# tv_b_gone_extended_schematic.net
KiCad netlist of a schematic drawn in EAGLE
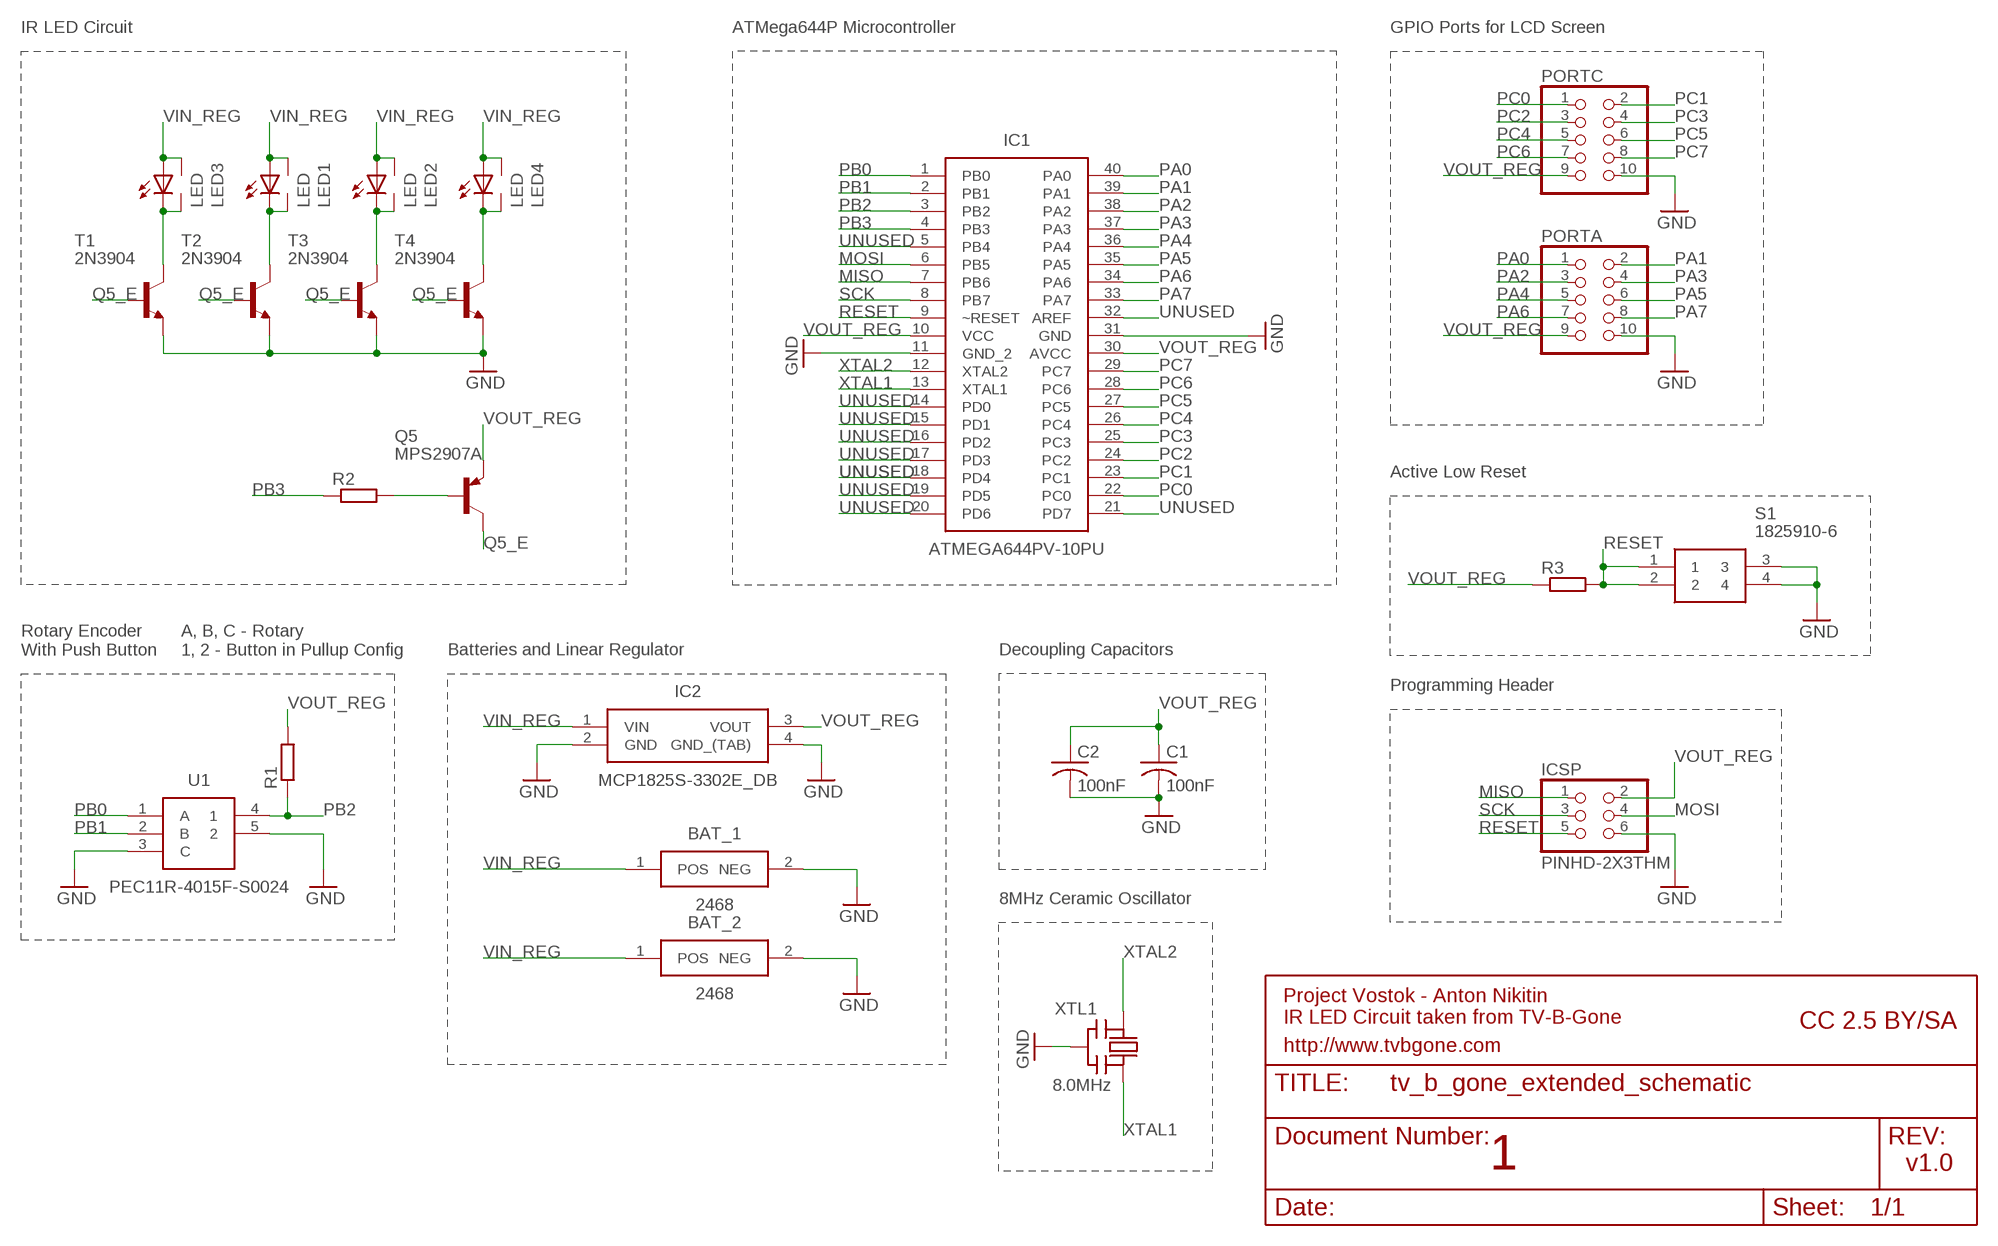
[diagram p0: schematic, sheet 1]

(export (version "E")
  (design (tool "Eeschema 10.0.6"))
  (components
    (comp (ref "BAT_1")
      (value "2468")
      (footprint "eagle-import:2468")
      (fields (field (name "RS_PART_NUMBER") "2794965"))
      (libsource (lib "eagle-import") (part "2468"))
    )
    (comp (ref "BAT_2")
      (value "2468")
      (footprint "eagle-import:2468")
      (fields (field (name "RS_PART_NUMBER") "2794965"))
      (libsource (lib "eagle-import") (part "2468"))
    )
    (comp (ref "C1")
      (value "100nF")
      (footprint "eagle-import:C025-025X050")
      (libsource (lib "eagle-import") (part "C-US025-025X050"))
    )
    (comp (ref "C2")
      (value "100nF")
      (footprint "eagle-import:C025-025X050")
      (libsource (lib "eagle-import") (part "C-US025-025X050"))
    )
    (comp (ref "IC1")
      (value "ATMEGA644PV-10PU")
      (footprint "eagle-import:DIP254P1524X483-40")
      (fields (field (name "RS_PART_NUMBER") "7380491P"))
      (libsource (lib "eagle-import") (part "ATMEGA644PV-10PU"))
    )
    (comp (ref "IC2")
      (value "MCP1825S-3302E_DB")
      (footprint "eagle-import:SOT230P700X180-4N")
      (fields
        (field (name "MANUFACTURER_PART_NUMBER") "MCP1825S-3302E/DB")
        (field (name "RS_PART_NUMBER") "9115520")
      )
      (libsource (lib "eagle-import") (part "MCP1825S-3302E_DB"))
    )
    (comp (ref "ICSP")
      (value "PINHD-2X3THM")
      (footprint "eagle-import:ISP6")
      (libsource (lib "eagle-import") (part "PINHD-2X3THM"))
    )
    (comp (ref "LED1")
      (value "LED")
      (footprint "eagle-import:5MM-SIDE")
      (libsource (lib "eagle-import") (part "LED"))
    )
    (comp (ref "LED2")
      (value "LED")
      (footprint "eagle-import:5MM-SIDE")
      (libsource (lib "eagle-import") (part "LED"))
    )
    (comp (ref "LED3")
      (value "LED")
      (footprint "eagle-import:5MM-SIDE")
      (libsource (lib "eagle-import") (part "LED"))
    )
    (comp (ref "LED4")
      (value "LED")
      (footprint "eagle-import:5MM-SIDE")
      (libsource (lib "eagle-import") (part "LED"))
    )
    (comp (ref "PORTA")
      (value "PINHD-2X5")
      (footprint "eagle-import:2X05")
      (libsource (lib "eagle-import") (part "PINHD-2X5"))
    )
    (comp (ref "PORTC")
      (value "PINHD-2X5")
      (footprint "eagle-import:2X05")
      (libsource (lib "eagle-import") (part "PINHD-2X5"))
    )
    (comp (ref "Q5")
      (value "MPS2907A")
      (footprint "eagle-import:TO92-CBE")
      (libsource (lib "eagle-import") (part "MPS2907A"))
    )
    (comp (ref "R1")
      (value "R-EU_0204/5")
      (footprint "eagle-import:0204_5")
      (libsource (lib "eagle-import") (part "resistor_348_R-EU_0204/5"))
    )
    (comp (ref "R2")
      (value "R-EU_0204/5")
      (footprint "eagle-import:0204_5")
      (libsource (lib "eagle-import") (part "resistor_348_R-EU_0204/5"))
    )
    (comp (ref "R3")
      (value "R-EU_0204/7")
      (footprint "eagle-import:0204_7")
      (libsource (lib "eagle-import") (part "R-EU_0204/7"))
    )
    (comp (ref "S1")
      (value "1825910-6")
      (footprint "eagle-import:1825910-6")
      (fields (field (name "RS_PART_NUMBER") "1613779"))
      (libsource (lib "eagle-import") (part "1825910-6"))
    )
    (comp (ref "T1")
      (value "2N3904")
      (footprint "eagle-import:TO92")
      (libsource (lib "eagle-import") (part "2N3904"))
    )
    (comp (ref "T2")
      (value "2N3904")
      (footprint "eagle-import:TO92")
      (libsource (lib "eagle-import") (part "2N3904"))
    )
    (comp (ref "T3")
      (value "2N3904")
      (footprint "eagle-import:TO92")
      (libsource (lib "eagle-import") (part "2N3904"))
    )
    (comp (ref "T4")
      (value "2N3904")
      (footprint "eagle-import:TO92")
      (libsource (lib "eagle-import") (part "2N3904"))
    )
    (comp (ref "U1")
      (value "PEC11R-4015F-S0024")
      (footprint "eagle-import:PEC12R-4XXXF-SXXXX_1")
      (fields (field (name "RS_PART_NUMBER") "7377739P"))
      (libsource (lib "eagle-import") (part "PEC11R-4015F-S0024"))
    )
    (comp (ref "XTL1")
      (value "8.0MHz")
      (footprint "eagle-import:CERM_OSC")
      (libsource (lib "eagle-import") (part "CERMOSCILL"))
    )
  )
  (nets
    (net (code "1") (name "/MISO") (class "Default")
      (node (ref "IC1") (pin "7") (pinfunction "PB6_7") (pintype "passive"))
      (node (ref "ICSP") (pin "1") (pinfunction "1_1") (pintype "passive"))
    )
    (net (code "2") (name "/MOSI") (class "Default")
      (node (ref "IC1") (pin "6") (pinfunction "PB5_6") (pintype "passive"))
      (node (ref "ICSP") (pin "4") (pinfunction "4_4") (pintype "passive"))
    )
    (net (code "3") (name "/PA0") (class "Default")
      (node (ref "IC1") (pin "40") (pinfunction "PA0_40") (pintype "passive"))
      (node (ref "PORTA") (pin "1") (pinfunction "1_1") (pintype "passive"))
    )
    (net (code "4") (name "/PA1") (class "Default")
      (node (ref "IC1") (pin "39") (pinfunction "PA1_39") (pintype "passive"))
      (node (ref "PORTA") (pin "2") (pinfunction "2_2") (pintype "passive"))
    )
    (net (code "5") (name "/PA2") (class "Default")
      (node (ref "IC1") (pin "38") (pinfunction "PA2_38") (pintype "passive"))
      (node (ref "PORTA") (pin "3") (pinfunction "3_3") (pintype "passive"))
    )
    (net (code "6") (name "/PA3") (class "Default")
      (node (ref "IC1") (pin "37") (pinfunction "PA3_37") (pintype "passive"))
      (node (ref "PORTA") (pin "4") (pinfunction "4_4") (pintype "passive"))
    )
    (net (code "7") (name "/PA4") (class "Default")
      (node (ref "IC1") (pin "36") (pinfunction "PA4_36") (pintype "passive"))
      (node (ref "PORTA") (pin "5") (pinfunction "5_5") (pintype "passive"))
    )
    (net (code "8") (name "/PA5") (class "Default")
      (node (ref "IC1") (pin "35") (pinfunction "PA5_35") (pintype "passive"))
      (node (ref "PORTA") (pin "6") (pinfunction "6_6") (pintype "passive"))
    )
    (net (code "9") (name "/PA6") (class "Default")
      (node (ref "IC1") (pin "34") (pinfunction "PA6_34") (pintype "passive"))
      (node (ref "PORTA") (pin "7") (pinfunction "7_7") (pintype "passive"))
    )
    (net (code "10") (name "/PA7") (class "Default")
      (node (ref "IC1") (pin "33") (pinfunction "PA7_33") (pintype "passive"))
      (node (ref "PORTA") (pin "8") (pinfunction "8_8") (pintype "passive"))
    )
    (net (code "11") (name "/PB0") (class "Default")
      (node (ref "IC1") (pin "1") (pinfunction "PB0_1") (pintype "passive"))
      (node (ref "U1") (pin "1") (pinfunction "A_1") (pintype "passive"))
    )
    (net (code "12") (name "/PB1") (class "Default")
      (node (ref "IC1") (pin "2") (pinfunction "PB1_2") (pintype "passive"))
      (node (ref "U1") (pin "2") (pinfunction "B_2") (pintype "passive"))
    )
    (net (code "13") (name "/PB2") (class "Default")
      (node (ref "IC1") (pin "3") (pinfunction "PB2_3") (pintype "passive"))
      (node (ref "R1") (pin "1") (pinfunction "1_1") (pintype "passive"))
      (node (ref "U1") (pin "4") (pinfunction "1_4") (pintype "passive"))
    )
    (net (code "14") (name "/PB3") (class "Default")
      (node (ref "IC1") (pin "4") (pinfunction "PB3_4") (pintype "passive"))
      (node (ref "R2") (pin "1") (pinfunction "1_1") (pintype "passive"))
    )
    (net (code "15") (name "/PC0") (class "Default")
      (node (ref "IC1") (pin "22") (pinfunction "PC0_22") (pintype "passive"))
      (node (ref "PORTC") (pin "1") (pinfunction "1_1") (pintype "passive"))
    )
    (net (code "16") (name "/PC1") (class "Default")
      (node (ref "IC1") (pin "23") (pinfunction "PC1_23") (pintype "passive"))
      (node (ref "PORTC") (pin "2") (pinfunction "2_2") (pintype "passive"))
    )
    (net (code "17") (name "/PC2") (class "Default")
      (node (ref "IC1") (pin "24") (pinfunction "PC2_24") (pintype "passive"))
      (node (ref "PORTC") (pin "3") (pinfunction "3_3") (pintype "passive"))
    )
    (net (code "18") (name "/PC3") (class "Default")
      (node (ref "IC1") (pin "25") (pinfunction "PC3_25") (pintype "passive"))
      (node (ref "PORTC") (pin "4") (pinfunction "4_4") (pintype "passive"))
    )
    (net (code "19") (name "/PC4") (class "Default")
      (node (ref "IC1") (pin "26") (pinfunction "PC4_26") (pintype "passive"))
      (node (ref "PORTC") (pin "5") (pinfunction "5_5") (pintype "passive"))
    )
    (net (code "20") (name "/PC5") (class "Default")
      (node (ref "IC1") (pin "27") (pinfunction "PC5_27") (pintype "passive"))
      (node (ref "PORTC") (pin "6") (pinfunction "6_6") (pintype "passive"))
    )
    (net (code "21") (name "/PC6") (class "Default")
      (node (ref "IC1") (pin "28") (pinfunction "PC6_28") (pintype "passive"))
      (node (ref "PORTC") (pin "7") (pinfunction "7_7") (pintype "passive"))
    )
    (net (code "22") (name "/PC7") (class "Default")
      (node (ref "IC1") (pin "29") (pinfunction "PC7_29") (pintype "passive"))
      (node (ref "PORTC") (pin "8") (pinfunction "8_8") (pintype "passive"))
    )
    (net (code "23") (name "/Q5_E") (class "Default")
      (node (ref "Q5") (pin "C") (pinfunction "C_C") (pintype "passive"))
      (node (ref "T1") (pin "2") (pinfunction "B_2") (pintype "passive"))
      (node (ref "T2") (pin "2") (pinfunction "B_2") (pintype "passive"))
      (node (ref "T3") (pin "2") (pinfunction "B_2") (pintype "passive"))
      (node (ref "T4") (pin "2") (pinfunction "B_2") (pintype "passive"))
    )
    (net (code "24") (name "/RESET") (class "Default")
      (node (ref "IC1") (pin "9") (pinfunction "~{RESET}_9") (pintype "passive"))
      (node (ref "ICSP") (pin "5") (pinfunction "5_5") (pintype "passive"))
      (node (ref "R3") (pin "2") (pinfunction "2_2") (pintype "passive"))
      (node (ref "S1") (pin "1") (pinfunction "1_1") (pintype "input"))
      (node (ref "S1") (pin "2") (pinfunction "2_2") (pintype "input"))
    )
    (net (code "25") (name "/SCK") (class "Default")
      (node (ref "IC1") (pin "8") (pinfunction "PB7_8") (pintype "passive"))
      (node (ref "ICSP") (pin "3") (pinfunction "3_3") (pintype "passive"))
    )
    (net (code "26") (name "/VIN_REG") (class "Default")
      (node (ref "BAT_1") (pin "1") (pinfunction "POS_1") (pintype "passive"))
      (node (ref "BAT_2") (pin "1") (pinfunction "POS_1") (pintype "passive"))
      (node (ref "IC2") (pin "1") (pinfunction "VIN_1") (pintype "input"))
      (node (ref "LED1") (pin "A") (pinfunction "A_A") (pintype "passive"))
      (node (ref "LED1") (pin "A2") (pinfunction "A1_A2") (pintype "passive"))
      (node (ref "LED2") (pin "A") (pinfunction "A_A") (pintype "passive"))
      (node (ref "LED2") (pin "A2") (pinfunction "A1_A2") (pintype "passive"))
      (node (ref "LED3") (pin "A") (pinfunction "A_A") (pintype "passive"))
      (node (ref "LED3") (pin "A2") (pinfunction "A1_A2") (pintype "passive"))
      (node (ref "LED4") (pin "A") (pinfunction "A_A") (pintype "passive"))
      (node (ref "LED4") (pin "A2") (pinfunction "A1_A2") (pintype "passive"))
    )
    (net (code "27") (name "/VOUT_REG") (class "Default")
      (node (ref "C1") (pin "1") (pinfunction "1_1") (pintype "passive"))
      (node (ref "C2") (pin "1") (pinfunction "1_1") (pintype "passive"))
      (node (ref "IC1") (pin "10") (pinfunction "VCC_10") (pintype "passive"))
      (node (ref "IC1") (pin "30") (pinfunction "AVCC_30") (pintype "passive"))
      (node (ref "IC2") (pin "3") (pinfunction "VOUT_3") (pintype "output"))
      (node (ref "ICSP") (pin "2") (pinfunction "2_2") (pintype "passive"))
      (node (ref "PORTA") (pin "9") (pinfunction "9_9") (pintype "passive"))
      (node (ref "PORTC") (pin "9") (pinfunction "9_9") (pintype "passive"))
      (node (ref "Q5") (pin "E") (pinfunction "E_E") (pintype "passive"))
      (node (ref "R1") (pin "2") (pinfunction "2_2") (pintype "passive"))
      (node (ref "R3") (pin "1") (pinfunction "1_1") (pintype "passive"))
    )
    (net (code "28") (name "/XTAL1") (class "Default")
      (node (ref "IC1") (pin "13") (pinfunction "XTAL1_13") (pintype "passive"))
      (node (ref "XTL1") (pin "P$3") (pinfunction "OUT_P$3") (pintype "bidirectional"))
    )
    (net (code "29") (name "/XTAL2") (class "Default")
      (node (ref "IC1") (pin "12") (pinfunction "XTAL2_12") (pintype "passive"))
      (node (ref "XTL1") (pin "P$1") (pinfunction "IN_P$1") (pintype "bidirectional"))
    )
    (net (code "30") (name "GND") (class "Default")
      (node (ref "BAT_1") (pin "2") (pinfunction "NEG_2") (pintype "passive"))
      (node (ref "BAT_2") (pin "2") (pinfunction "NEG_2") (pintype "passive"))
      (node (ref "C1") (pin "2") (pinfunction "2_2") (pintype "passive"))
      (node (ref "C2") (pin "2") (pinfunction "2_2") (pintype "passive"))
      (node (ref "IC1") (pin "11") (pinfunction "GND_2_11") (pintype "passive"))
      (node (ref "IC1") (pin "31") (pinfunction "GND_31") (pintype "passive"))
      (node (ref "IC2") (pin "2") (pinfunction "GND_2") (pintype "power_in"))
      (node (ref "IC2") (pin "4") (pinfunction "GND_(TAB)_4") (pintype "power_in"))
      (node (ref "ICSP") (pin "6") (pinfunction "6_6") (pintype "passive"))
      (node (ref "PORTA") (pin "10") (pinfunction "10_10") (pintype "passive"))
      (node (ref "PORTC") (pin "10") (pinfunction "10_10") (pintype "passive"))
      (node (ref "S1") (pin "3") (pinfunction "3_3") (pintype "input"))
      (node (ref "S1") (pin "4") (pinfunction "4_4") (pintype "input"))
      (node (ref "T1") (pin "3") (pinfunction "E_3") (pintype "passive"))
      (node (ref "T2") (pin "3") (pinfunction "E_3") (pintype "passive"))
      (node (ref "T3") (pin "3") (pinfunction "E_3") (pintype "passive"))
      (node (ref "T4") (pin "3") (pinfunction "E_3") (pintype "passive"))
      (node (ref "U1") (pin "3") (pinfunction "C_3") (pintype "passive"))
      (node (ref "U1") (pin "5") (pinfunction "2_5") (pintype "passive"))
      (node (ref "XTL1") (pin "P$2") (pinfunction "GND_P$2") (pintype "bidirectional"))
    )
    (net (code "31") (name "Net-(LED1-C)") (class "Default")
      (node (ref "LED1") (pin "K") (pinfunction "C_K") (pintype "passive"))
      (node (ref "LED1") (pin "K2") (pinfunction "C1_K2") (pintype "passive"))
      (node (ref "T2") (pin "1") (pinfunction "C_1") (pintype "passive"))
    )
    (net (code "32") (name "Net-(LED2-C)") (class "Default")
      (node (ref "LED2") (pin "K") (pinfunction "C_K") (pintype "passive"))
      (node (ref "LED2") (pin "K2") (pinfunction "C1_K2") (pintype "passive"))
      (node (ref "T3") (pin "1") (pinfunction "C_1") (pintype "passive"))
    )
    (net (code "33") (name "Net-(LED3-C)") (class "Default")
      (node (ref "LED3") (pin "K") (pinfunction "C_K") (pintype "passive"))
      (node (ref "LED3") (pin "K2") (pinfunction "C1_K2") (pintype "passive"))
      (node (ref "T1") (pin "1") (pinfunction "C_1") (pintype "passive"))
    )
    (net (code "34") (name "Net-(LED4-C)") (class "Default")
      (node (ref "LED4") (pin "K") (pinfunction "C_K") (pintype "passive"))
      (node (ref "LED4") (pin "K2") (pinfunction "C1_K2") (pintype "passive"))
      (node (ref "T4") (pin "1") (pinfunction "C_1") (pintype "passive"))
    )
    (net (code "35") (name "Net-(Q5-PadB)") (class "Default")
      (node (ref "Q5") (pin "B") (pinfunction "B_B") (pintype "passive"))
      (node (ref "R2") (pin "2") (pinfunction "2_2") (pintype "passive"))
    )
    (net (code "36") (name "unconnected-(IC1-AREF-Pad32)") (class "Default")
      (node (ref "IC1") (pin "32") (pinfunction "AREF_32") (pintype "passive"))
    )
    (net (code "37") (name "unconnected-(IC1-PB4-Pad5)") (class "Default")
      (node (ref "IC1") (pin "5") (pinfunction "PB4_5") (pintype "passive"))
    )
    (net (code "38") (name "unconnected-(IC1-PD0-Pad14)") (class "Default")
      (node (ref "IC1") (pin "14") (pinfunction "PD0_14") (pintype "passive"))
    )
    (net (code "39") (name "unconnected-(IC1-PD1-Pad15)") (class "Default")
      (node (ref "IC1") (pin "15") (pinfunction "PD1_15") (pintype "passive"))
    )
    (net (code "40") (name "unconnected-(IC1-PD2-Pad16)") (class "Default")
      (node (ref "IC1") (pin "16") (pinfunction "PD2_16") (pintype "passive"))
    )
    (net (code "41") (name "unconnected-(IC1-PD3-Pad17)") (class "Default")
      (node (ref "IC1") (pin "17") (pinfunction "PD3_17") (pintype "passive"))
    )
    (net (code "42") (name "unconnected-(IC1-PD4-Pad18)") (class "Default")
      (node (ref "IC1") (pin "18") (pinfunction "PD4_18") (pintype "passive"))
    )
    (net (code "43") (name "unconnected-(IC1-PD5-Pad19)") (class "Default")
      (node (ref "IC1") (pin "19") (pinfunction "PD5_19") (pintype "passive"))
    )
    (net (code "44") (name "unconnected-(IC1-PD6-Pad20)") (class "Default")
      (node (ref "IC1") (pin "20") (pinfunction "PD6_20") (pintype "passive"))
    )
    (net (code "45") (name "unconnected-(IC1-PD7-Pad21)") (class "Default")
      (node (ref "IC1") (pin "21") (pinfunction "PD7_21") (pintype "passive"))
    )
  )
)
